# power.net
KiCad netlist of a schematic drawn in EAGLE
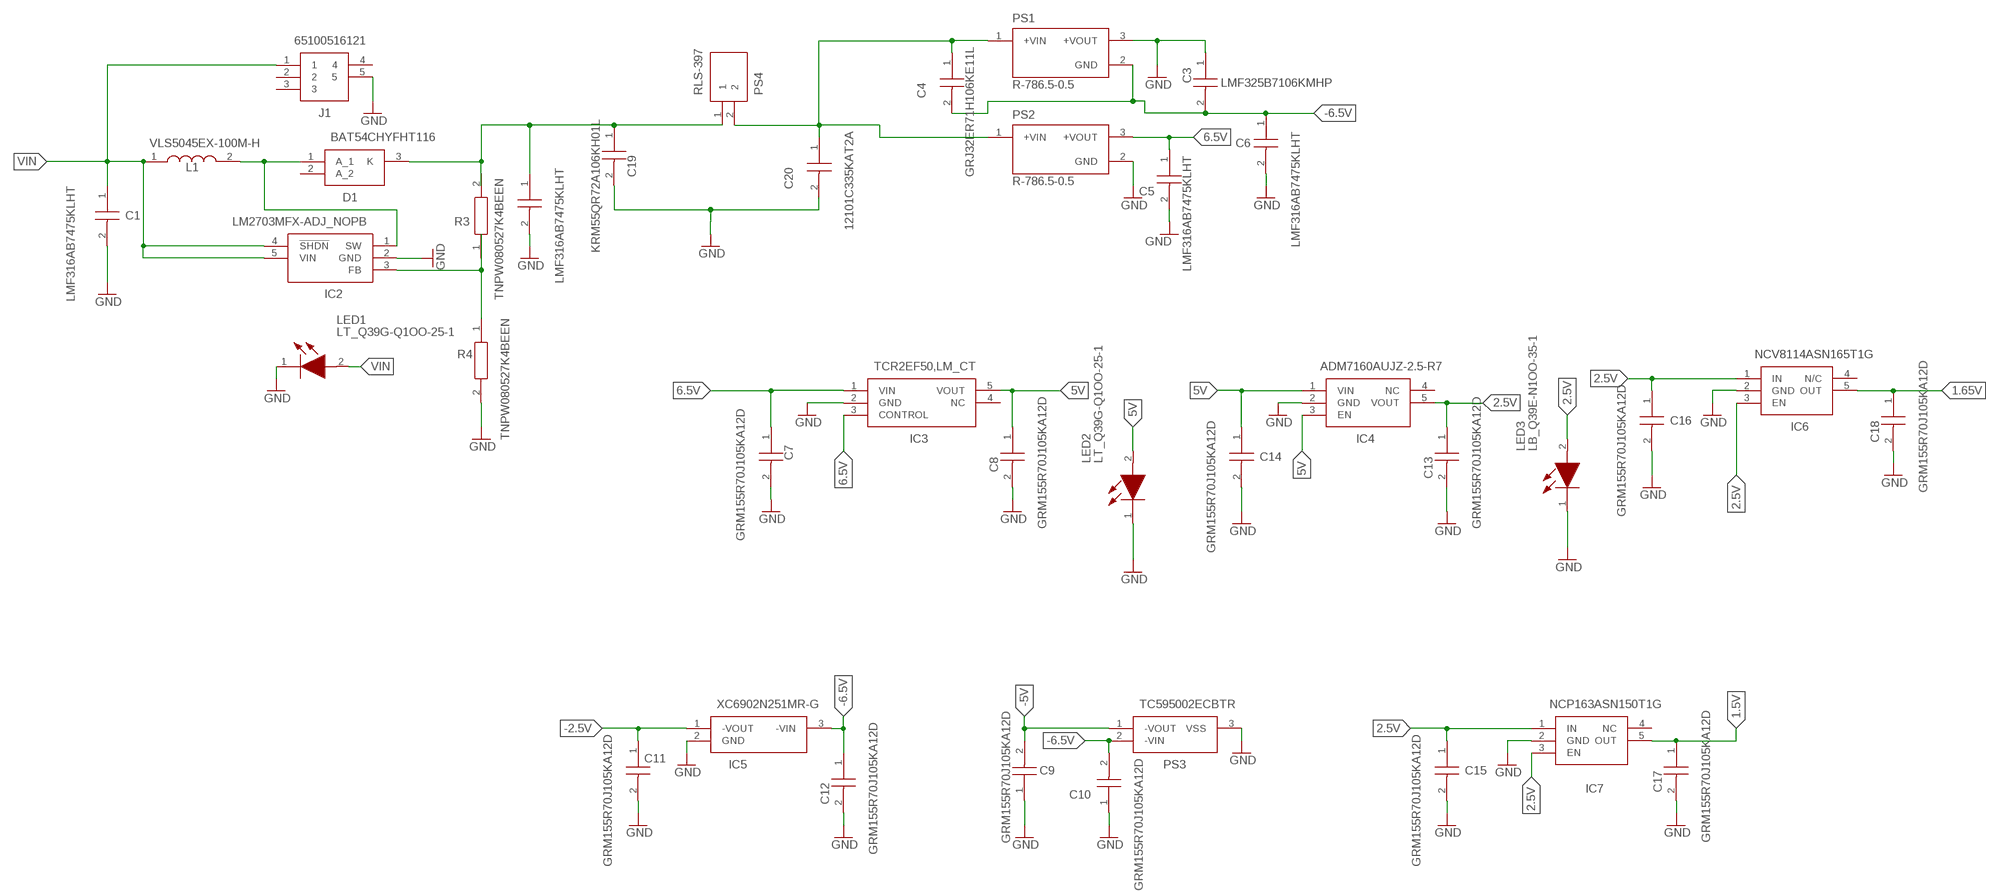
[diagram p0: schematic, sheet 1]

(export (version "E")
  (design (tool "Eeschema 10.0.6"))
  (components
    (comp (ref "C1")
      (value "LMF316AB7475KLHT")
      (footprint "eagle-import:CAPC3216X180N")
      (fields (field (name "MOUSER_PART_NUMBER") "963-LMF316AB7475KLHT"))
      (libsource (lib "eagle-import") (part "LMF316AB7475KLHT"))
    )
    (comp (ref "C2")
      (value "LMF316AB7475KLHT")
      (footprint "eagle-import:CAPC3216X180N")
      (fields (field (name "MOUSER_PART_NUMBER") "963-LMF316AB7475KLHT"))
      (libsource (lib "eagle-import") (part "LMF316AB7475KLHT"))
    )
    (comp (ref "C3")
      (value "LMF325B7106KMHP")
      (footprint "eagle-import:CAPC3225X270N")
      (fields (field (name "MOUSER_PART_NUMBER") "963-LMF325B7106KMHP"))
      (libsource (lib "eagle-import") (part "LMF325B7106KMHP"))
    )
    (comp (ref "C4")
      (value "GRJ32ER71H106KE11L")
      (footprint "eagle-import:CAPC3225X280N")
      (fields (field (name "MOUSER_PART_NUMBER") "81-GRJ32ER71H106KE1L"))
      (libsource (lib "eagle-import") (part "GRJ32ER71H106KE11L"))
    )
    (comp (ref "C5")
      (value "LMF316AB7475KLHT")
      (footprint "eagle-import:CAPC3216X180N")
      (fields (field (name "MOUSER_PART_NUMBER") "963-LMF316AB7475KLHT"))
      (libsource (lib "eagle-import") (part "LMF316AB7475KLHT"))
    )
    (comp (ref "C6")
      (value "LMF316AB7475KLHT")
      (footprint "eagle-import:CAPC3216X180N")
      (fields (field (name "MOUSER_PART_NUMBER") "963-LMF316AB7475KLHT"))
      (libsource (lib "eagle-import") (part "LMF316AB7475KLHT"))
    )
    (comp (ref "C7")
      (value "GRM155R70J105KA12D")
      (footprint "eagle-import:CAPC1005X55N")
      (fields (field (name "MOUSER_PART_NUMBER") "81-GRM155R70J105KA2D"))
      (libsource (lib "eagle-import") (part "GRM155R70J105KA12D"))
    )
    (comp (ref "C8")
      (value "GRM155R70J105KA12D")
      (footprint "eagle-import:CAPC1005X55N")
      (fields (field (name "MOUSER_PART_NUMBER") "81-GRM155R70J105KA2D"))
      (libsource (lib "eagle-import") (part "GRM155R70J105KA12D"))
    )
    (comp (ref "C9")
      (value "GRM155R70J105KA12D")
      (footprint "eagle-import:CAPC1005X55N")
      (fields (field (name "MOUSER_PART_NUMBER") "81-GRM155R70J105KA2D"))
      (libsource (lib "eagle-import") (part "GRM155R70J105KA12D"))
    )
    (comp (ref "C10")
      (value "GRM155R70J105KA12D")
      (footprint "eagle-import:CAPC1005X55N")
      (fields (field (name "MOUSER_PART_NUMBER") "81-GRM155R70J105KA2D"))
      (libsource (lib "eagle-import") (part "GRM155R70J105KA12D"))
    )
    (comp (ref "C11")
      (value "GRM155R70J105KA12D")
      (footprint "eagle-import:CAPC1005X55N")
      (fields (field (name "MOUSER_PART_NUMBER") "81-GRM155R70J105KA2D"))
      (libsource (lib "eagle-import") (part "GRM155R70J105KA12D"))
    )
    (comp (ref "C12")
      (value "GRM155R70J105KA12D")
      (footprint "eagle-import:CAPC1005X55N")
      (fields (field (name "MOUSER_PART_NUMBER") "81-GRM155R70J105KA2D"))
      (libsource (lib "eagle-import") (part "GRM155R70J105KA12D"))
    )
    (comp (ref "C13")
      (value "GRM155R70J105KA12D")
      (footprint "eagle-import:CAPC1005X55N")
      (fields (field (name "MOUSER_PART_NUMBER") "81-GRM155R70J105KA2D"))
      (libsource (lib "eagle-import") (part "GRM155R70J105KA12D"))
    )
    (comp (ref "C14")
      (value "GRM155R70J105KA12D")
      (footprint "eagle-import:CAPC1005X55N")
      (fields (field (name "MOUSER_PART_NUMBER") "81-GRM155R70J105KA2D"))
      (libsource (lib "eagle-import") (part "GRM155R70J105KA12D"))
    )
    (comp (ref "C15")
      (value "GRM155R70J105KA12D")
      (footprint "eagle-import:CAPC1005X55N")
      (fields (field (name "MOUSER_PART_NUMBER") "81-GRM155R70J105KA2D"))
      (libsource (lib "eagle-import") (part "GRM155R70J105KA12D"))
    )
    (comp (ref "C16")
      (value "GRM155R70J105KA12D")
      (footprint "eagle-import:CAPC1005X55N")
      (fields (field (name "MOUSER_PART_NUMBER") "81-GRM155R70J105KA2D"))
      (libsource (lib "eagle-import") (part "GRM155R70J105KA12D"))
    )
    (comp (ref "C17")
      (value "GRM155R70J105KA12D")
      (footprint "eagle-import:CAPC1005X55N")
      (fields (field (name "MOUSER_PART_NUMBER") "81-GRM155R70J105KA2D"))
      (libsource (lib "eagle-import") (part "GRM155R70J105KA12D"))
    )
    (comp (ref "C18")
      (value "GRM155R70J105KA12D")
      (footprint "eagle-import:CAPC1005X55N")
      (fields (field (name "MOUSER_PART_NUMBER") "81-GRM155R70J105KA2D"))
      (libsource (lib "eagle-import") (part "GRM155R70J105KA12D"))
    )
    (comp (ref "C19")
      (value "KRM55QR72A106KH01L")
      (footprint "eagle-import:CAPC6153X390N")
      (fields (field (name "MOUSER_PART_NUMBER") "81-KRM55QR72A106KH1L"))
      (libsource (lib "eagle-import") (part "KRM55QR72A106KH01L"))
    )
    (comp (ref "C20")
      (value "12101C335KAT2A")
      (footprint "eagle-import:CAPC3325X279N")
      (fields (field (name "MOUSER_PART_NUMBER") "581-12101C335KAT2A"))
      (libsource (lib "eagle-import") (part "12101C335KAT2A"))
    )
    (comp (ref "D1")
      (value "BAT54CHYFHT116")
      (footprint "eagle-import:SOT95P240X115-3N")
      (fields (field (name "MOUSER_PART_NUMBER") "755-BAT54CHYFHT116"))
      (libsource (lib "eagle-import") (part "BAT54CHYFHT116"))
    )
    (comp (ref "IC2")
      (value "LM2703MFX-ADJ_NOPB")
      (footprint "eagle-import:SOT95P280X145-5N")
      (fields
        (field (name "ARROW_PART_NUMBER") "LM2703MFX-ADJ/NOPB")
        (field (name "MOUSER_PART_NUMBER") "926-LM2703MFXADJNOPB")
      )
      (libsource (lib "eagle-import") (part "LM2703MFX-ADJ_NOPB"))
    )
    (comp (ref "IC3")
      (value "TCR2EF50,LM_CT")
      (footprint "eagle-import:TCR2EF50LMCT")
      (fields
        (field (name "MANUFACTURER_PART_NUMBER") "TCR2EF50,LM(CT")
        (field (name "MOUSER_PART_NUMBER") "757-TCR2EF50LMCT")
      )
      (libsource (lib "eagle-import") (part "TCR2EF50,LM_CT"))
    )
    (comp (ref "IC4")
      (value "ADM7160AUJZ-2.5-R7")
      (footprint "eagle-import:SOT95P280X100-5N")
      (fields (field (name "MOUSER_PART_NUMBER") "584-ADM7160AUJZ2.5R7"))
      (libsource (lib "eagle-import") (part "ADM7160AUJZ-2.5-R7"))
    )
    (comp (ref "IC5")
      (value "XC6902N251MR-G")
      (footprint "eagle-import:SOT95P280X130-3N")
      (fields (field (name "MOUSER_PART_NUMBER") "865-XC6902N251MR-G"))
      (libsource (lib "eagle-import") (part "XC6902N251MR-G"))
    )
    (comp (ref "IC6")
      (value "NCV8114ASN165T1G")
      (footprint "eagle-import:SOT95P275X110-5N")
      (fields (field (name "MOUSER_PART_NUMBER") "863-NCV8114ASN165T1G"))
      (libsource (lib "eagle-import") (part "NCV8114ASN165T1G"))
    )
    (comp (ref "IC7")
      (value "NCP163ASN150T1G")
      (footprint "eagle-import:SOT95P280X145-5N")
      (fields (field (name "MOUSER_PART_NUMBER") "863-NCP163ASN150T1G"))
      (libsource (lib "eagle-import") (part "NCP163ASN150T1G"))
    )
    (comp (ref "J1")
      (value "65100516121")
      (footprint "eagle-import:65100516121")
      (fields (field (name "MOUSER_PART_NUMBER") "710-65100516121"))
      (libsource (lib "eagle-import") (part "65100516121"))
    )
    (comp (ref "L1")
      (value "VLS5045EX-100M-H")
      (footprint "eagle-import:VLS5045EX330M")
      (fields (field (name "MOUSER_PART_NUMBER") "810-VLS5045EX-100M-H"))
      (libsource (lib "eagle-import") (part "VLS5045EX-100M-H"))
    )
    (comp (ref "LED1")
      (value "LT_Q39G-Q1OO-25-1")
      (footprint "eagle-import:LEDC1608X40N")
      (fields
        (field (name "MANUFACTURER_PART_NUMBER") "LT Q39G-Q1OO-25-1")
        (field (name "MOUSER_PART_NUMBER") "720-LTQ39GQ1S22515")
      )
      (libsource (lib "eagle-import") (part "LT_Q39G-Q1OO-25-1"))
    )
    (comp (ref "LED2")
      (value "LT_Q39G-Q1OO-25-1")
      (footprint "eagle-import:LEDC1608X40N")
      (fields
        (field (name "MANUFACTURER_PART_NUMBER") "LT Q39G-Q1OO-25-1")
        (field (name "MOUSER_PART_NUMBER") "720-LTQ39GQ1S22515")
      )
      (libsource (lib "eagle-import") (part "LT_Q39G-Q1OO-25-1"))
    )
    (comp (ref "LED3")
      (value "LB_Q39E-N1OO-35-1")
      (footprint "eagle-import:LEDC1608X40N")
      (fields
        (field (name "MANUFACTURER_PART_NUMBER") "LB Q39E-N1OO-35-1")
        (field (name "MOUSER_PART_NUMBER") "720-LBQ39EN1P1351")
      )
      (libsource (lib "eagle-import") (part "LB_Q39E-N1OO-35-1"))
    )
    (comp (ref "PS1")
      (value "R-786.5-0.5")
      (footprint "eagle-import:CONV_R-786.5-0.5")
      (fields (field (name "DIGI-KEY_PART_NUMBER") "945-1039-ND") (field (name "MF") "Recom Power"))
      (libsource (lib "eagle-import") (part "R-786.5-0.5"))
    )
    (comp (ref "PS2")
      (value "R-786.5-0.5")
      (footprint "eagle-import:CONV_R-786.5-0.5")
      (fields (field (name "DIGI-KEY_PART_NUMBER") "945-1039-ND") (field (name "MF") "Recom Power"))
      (libsource (lib "eagle-import") (part "R-786.5-0.5"))
    )
    (comp (ref "PS3")
      (value "TC595002ECBTR")
      (footprint "eagle-import:SOT95P275X130-3N")
      (fields (field (name "MOUSER_PART_NUMBER") "579-TC595002ECBTR"))
      (libsource (lib "eagle-import") (part "TC595002ECBTR"))
    )
    (comp (ref "PS4")
      (value "RLS-397")
      (footprint "eagle-import:RLS397")
      (fields (field (name "MOUSER_PART_NUMBER") "919-RLS-397"))
      (libsource (lib "eagle-import") (part "RLS-397"))
    )
    (comp (ref "R3")
      (value "TNPW080527K4BEEN")
      (footprint "eagle-import:RESC2012X55N")
      (fields (field (name "MOUSER_PART_NUMBER") "71-TNPW080527K4BEEN"))
      (libsource (lib "eagle-import") (part "TNPW080527K4BEEN"))
    )
    (comp (ref "R4")
      (value "TNPW080527K4BEEN")
      (footprint "eagle-import:RESC2012X55N")
      (fields (field (name "MOUSER_PART_NUMBER") "71-TNPW080527K4BEEN"))
      (libsource (lib "eagle-import") (part "TNPW080527K4BEEN"))
    )
  )
  (nets
    (net (code "1") (name "-2.5V") (class "Default")
      (node (ref "C11") (pin "1") (pinfunction "1_1") (pintype "bidirectional"))
      (node (ref "IC5") (pin "1") (pinfunction "-VOUT_1") (pintype "bidirectional"))
    )
    (net (code "2") (name "-5V") (class "Default")
      (node (ref "C9") (pin "2") (pinfunction "2_2") (pintype "bidirectional"))
      (node (ref "PS3") (pin "1") (pinfunction "-VOUT_1") (pintype "output"))
    )
    (net (code "3") (name "-6.5V") (class "Default")
      (node (ref "C10") (pin "2") (pinfunction "2_2") (pintype "bidirectional"))
      (node (ref "C12") (pin "1") (pinfunction "1_1") (pintype "bidirectional"))
      (node (ref "C3") (pin "2") (pinfunction "2_2") (pintype "bidirectional"))
      (node (ref "C4") (pin "2") (pinfunction "2_2") (pintype "bidirectional"))
      (node (ref "C6") (pin "1") (pinfunction "1_1") (pintype "bidirectional"))
      (node (ref "IC5") (pin "3") (pinfunction "-VIN_3") (pintype "bidirectional"))
      (node (ref "PS1") (pin "2") (pinfunction "GND_2") (pintype "power_in"))
      (node (ref "PS3") (pin "2") (pinfunction "-VIN_2") (pintype "input"))
    )
    (net (code "4") (name "1.5V") (class "Default")
      (node (ref "C17") (pin "1") (pinfunction "1_1") (pintype "bidirectional"))
      (node (ref "IC7") (pin "5") (pinfunction "OUT_5") (pintype "bidirectional"))
    )
    (net (code "5") (name "1.65V") (class "Default")
      (node (ref "C18") (pin "1") (pinfunction "1_1") (pintype "bidirectional"))
      (node (ref "IC6") (pin "5") (pinfunction "OUT_5") (pintype "bidirectional"))
    )
    (net (code "6") (name "2.5V") (class "Default")
      (node (ref "C13") (pin "1") (pinfunction "1_1") (pintype "bidirectional"))
      (node (ref "C15") (pin "1") (pinfunction "1_1") (pintype "bidirectional"))
      (node (ref "C16") (pin "1") (pinfunction "1_1") (pintype "bidirectional"))
      (node (ref "IC4") (pin "5") (pinfunction "VOUT_5") (pintype "bidirectional"))
      (node (ref "IC6") (pin "1") (pinfunction "IN_1") (pintype "bidirectional"))
      (node (ref "IC6") (pin "3") (pinfunction "EN_3") (pintype "bidirectional"))
      (node (ref "IC7") (pin "1") (pinfunction "IN_1") (pintype "bidirectional"))
      (node (ref "IC7") (pin "3") (pinfunction "EN_3") (pintype "bidirectional"))
      (node (ref "LED3") (pin "2") (pinfunction "A_2") (pintype "bidirectional"))
    )
    (net (code "7") (name "5V") (class "Default")
      (node (ref "C14") (pin "1") (pinfunction "1_1") (pintype "bidirectional"))
      (node (ref "C8") (pin "1") (pinfunction "1_1") (pintype "bidirectional"))
      (node (ref "IC3") (pin "5") (pinfunction "VOUT_5") (pintype "bidirectional"))
      (node (ref "IC4") (pin "1") (pinfunction "VIN_1") (pintype "bidirectional"))
      (node (ref "IC4") (pin "3") (pinfunction "EN_3") (pintype "bidirectional"))
      (node (ref "LED2") (pin "2") (pinfunction "A_2") (pintype "bidirectional"))
    )
    (net (code "8") (name "6.5V") (class "Default")
      (node (ref "C5") (pin "1") (pinfunction "1_1") (pintype "bidirectional"))
      (node (ref "C7") (pin "1") (pinfunction "1_1") (pintype "bidirectional"))
      (node (ref "IC3") (pin "1") (pinfunction "VIN_1") (pintype "bidirectional"))
      (node (ref "IC3") (pin "3") (pinfunction "CONTROL_3") (pintype "bidirectional"))
      (node (ref "PS2") (pin "3") (pinfunction "+VOUT_3") (pintype "output"))
    )
    (net (code "9") (name "GND") (class "Default")
      (node (ref "C1") (pin "2") (pinfunction "2_2") (pintype "bidirectional"))
      (node (ref "C10") (pin "1") (pinfunction "1_1") (pintype "bidirectional"))
      (node (ref "C11") (pin "2") (pinfunction "2_2") (pintype "bidirectional"))
      (node (ref "C12") (pin "2") (pinfunction "2_2") (pintype "bidirectional"))
      (node (ref "C13") (pin "2") (pinfunction "2_2") (pintype "bidirectional"))
      (node (ref "C14") (pin "2") (pinfunction "2_2") (pintype "bidirectional"))
      (node (ref "C15") (pin "2") (pinfunction "2_2") (pintype "bidirectional"))
      (node (ref "C16") (pin "2") (pinfunction "2_2") (pintype "bidirectional"))
      (node (ref "C17") (pin "2") (pinfunction "2_2") (pintype "bidirectional"))
      (node (ref "C18") (pin "2") (pinfunction "2_2") (pintype "bidirectional"))
      (node (ref "C19") (pin "2") (pinfunction "2_2") (pintype "bidirectional"))
      (node (ref "C2") (pin "2") (pinfunction "2_2") (pintype "bidirectional"))
      (node (ref "C20") (pin "2") (pinfunction "2_2") (pintype "bidirectional"))
      (node (ref "C3") (pin "1") (pinfunction "1_1") (pintype "bidirectional"))
      (node (ref "C5") (pin "2") (pinfunction "2_2") (pintype "bidirectional"))
      (node (ref "C6") (pin "2") (pinfunction "2_2") (pintype "bidirectional"))
      (node (ref "C7") (pin "2") (pinfunction "2_2") (pintype "bidirectional"))
      (node (ref "C8") (pin "2") (pinfunction "2_2") (pintype "bidirectional"))
      (node (ref "C9") (pin "1") (pinfunction "1_1") (pintype "bidirectional"))
      (node (ref "IC2") (pin "2") (pinfunction "GND_2") (pintype "bidirectional"))
      (node (ref "IC3") (pin "2") (pinfunction "GND_2") (pintype "bidirectional"))
      (node (ref "IC4") (pin "2") (pinfunction "GND_2") (pintype "bidirectional"))
      (node (ref "IC5") (pin "2") (pinfunction "GND_2") (pintype "bidirectional"))
      (node (ref "IC6") (pin "2") (pinfunction "GND_2") (pintype "bidirectional"))
      (node (ref "IC7") (pin "2") (pinfunction "GND_2") (pintype "bidirectional"))
      (node (ref "J1") (pin "5") (pinfunction "5_5") (pintype "bidirectional"))
      (node (ref "LED1") (pin "1") (pinfunction "K_1") (pintype "bidirectional"))
      (node (ref "LED2") (pin "1") (pinfunction "K_1") (pintype "bidirectional"))
      (node (ref "LED3") (pin "1") (pinfunction "K_1") (pintype "bidirectional"))
      (node (ref "PS1") (pin "3") (pinfunction "+VOUT_3") (pintype "output"))
      (node (ref "PS2") (pin "2") (pinfunction "GND_2") (pintype "power_in"))
      (node (ref "PS3") (pin "3") (pinfunction "VSS_3") (pintype "power_in"))
      (node (ref "R4") (pin "2") (pinfunction "2_2") (pintype "bidirectional"))
    )
    (net (code "10") (name "Net-(D1-A_1)") (class "Default")
      (node (ref "D1") (pin "1") (pinfunction "A_1_1") (pintype "bidirectional"))
      (node (ref "IC2") (pin "1") (pinfunction "SW_1") (pintype "bidirectional"))
      (node (ref "L1") (pin "2") (pinfunction "2_2") (pintype "bidirectional"))
    )
    (net (code "11") (name "Net-(D1-K)") (class "Default")
      (node (ref "C19") (pin "1") (pinfunction "1_1") (pintype "bidirectional"))
      (node (ref "C2") (pin "1") (pinfunction "1_1") (pintype "bidirectional"))
      (node (ref "D1") (pin "3") (pinfunction "K_3") (pintype "bidirectional"))
      (node (ref "PS4") (pin "1") (pinfunction "1_1") (pintype "bidirectional"))
      (node (ref "R3") (pin "2") (pinfunction "2_2") (pintype "bidirectional"))
    )
    (net (code "12") (name "Net-(IC2-FB)") (class "Default")
      (node (ref "IC2") (pin "3") (pinfunction "FB_3") (pintype "bidirectional"))
      (node (ref "R3") (pin "1") (pinfunction "1_1") (pintype "bidirectional"))
      (node (ref "R4") (pin "1") (pinfunction "1_1") (pintype "bidirectional"))
    )
    (net (code "13") (name "Net-(PS1-+VIN)") (class "Default")
      (node (ref "C20") (pin "1") (pinfunction "1_1") (pintype "bidirectional"))
      (node (ref "C4") (pin "1") (pinfunction "1_1") (pintype "bidirectional"))
      (node (ref "PS1") (pin "1") (pinfunction "+VIN_1") (pintype "input"))
      (node (ref "PS2") (pin "1") (pinfunction "+VIN_1") (pintype "input"))
      (node (ref "PS4") (pin "2") (pinfunction "2_2") (pintype "bidirectional"))
    )
    (net (code "14") (name "VIN") (class "Default")
      (node (ref "C1") (pin "1") (pinfunction "1_1") (pintype "bidirectional"))
      (node (ref "IC2") (pin "4") (pinfunction "~{SHDN}_4") (pintype "bidirectional"))
      (node (ref "IC2") (pin "5") (pinfunction "VIN_5") (pintype "bidirectional"))
      (node (ref "J1") (pin "1") (pinfunction "1_1") (pintype "bidirectional"))
      (node (ref "L1") (pin "1") (pinfunction "1_1") (pintype "bidirectional"))
      (node (ref "LED1") (pin "2") (pinfunction "A_2") (pintype "bidirectional"))
    )
    (net (code "15") (name "unconnected-(D1-A_2-Pad2)") (class "Default")
      (node (ref "D1") (pin "2") (pinfunction "A_2_2") (pintype "bidirectional"))
    )
    (net (code "16") (name "unconnected-(IC3-NC-Pad4)") (class "Default")
      (node (ref "IC3") (pin "4") (pinfunction "NC_4") (pintype "no_connect"))
    )
    (net (code "17") (name "unconnected-(IC4-NC-Pad4)") (class "Default")
      (node (ref "IC4") (pin "4") (pinfunction "NC_4") (pintype "no_connect"))
    )
    (net (code "18") (name "unconnected-(IC6-N{slash}C-Pad4)") (class "Default")
      (node (ref "IC6") (pin "4") (pinfunction "N/C_4") (pintype "no_connect"))
    )
    (net (code "19") (name "unconnected-(IC7-NC-Pad4)") (class "Default")
      (node (ref "IC7") (pin "4") (pinfunction "NC_4") (pintype "no_connect"))
    )
    (net (code "20") (name "unconnected-(J1-Pad2)") (class "Default")
      (node (ref "J1") (pin "2") (pinfunction "2_2") (pintype "bidirectional"))
    )
    (net (code "21") (name "unconnected-(J1-Pad3)") (class "Default")
      (node (ref "J1") (pin "3") (pinfunction "3_3") (pintype "bidirectional"))
    )
    (net (code "22") (name "unconnected-(J1-Pad4)") (class "Default")
      (node (ref "J1") (pin "4") (pinfunction "4_4") (pintype "bidirectional"))
    )
  )
)
